# ardSCSInoV2.net
KiCad netlist of a schematic drawn in EAGLE
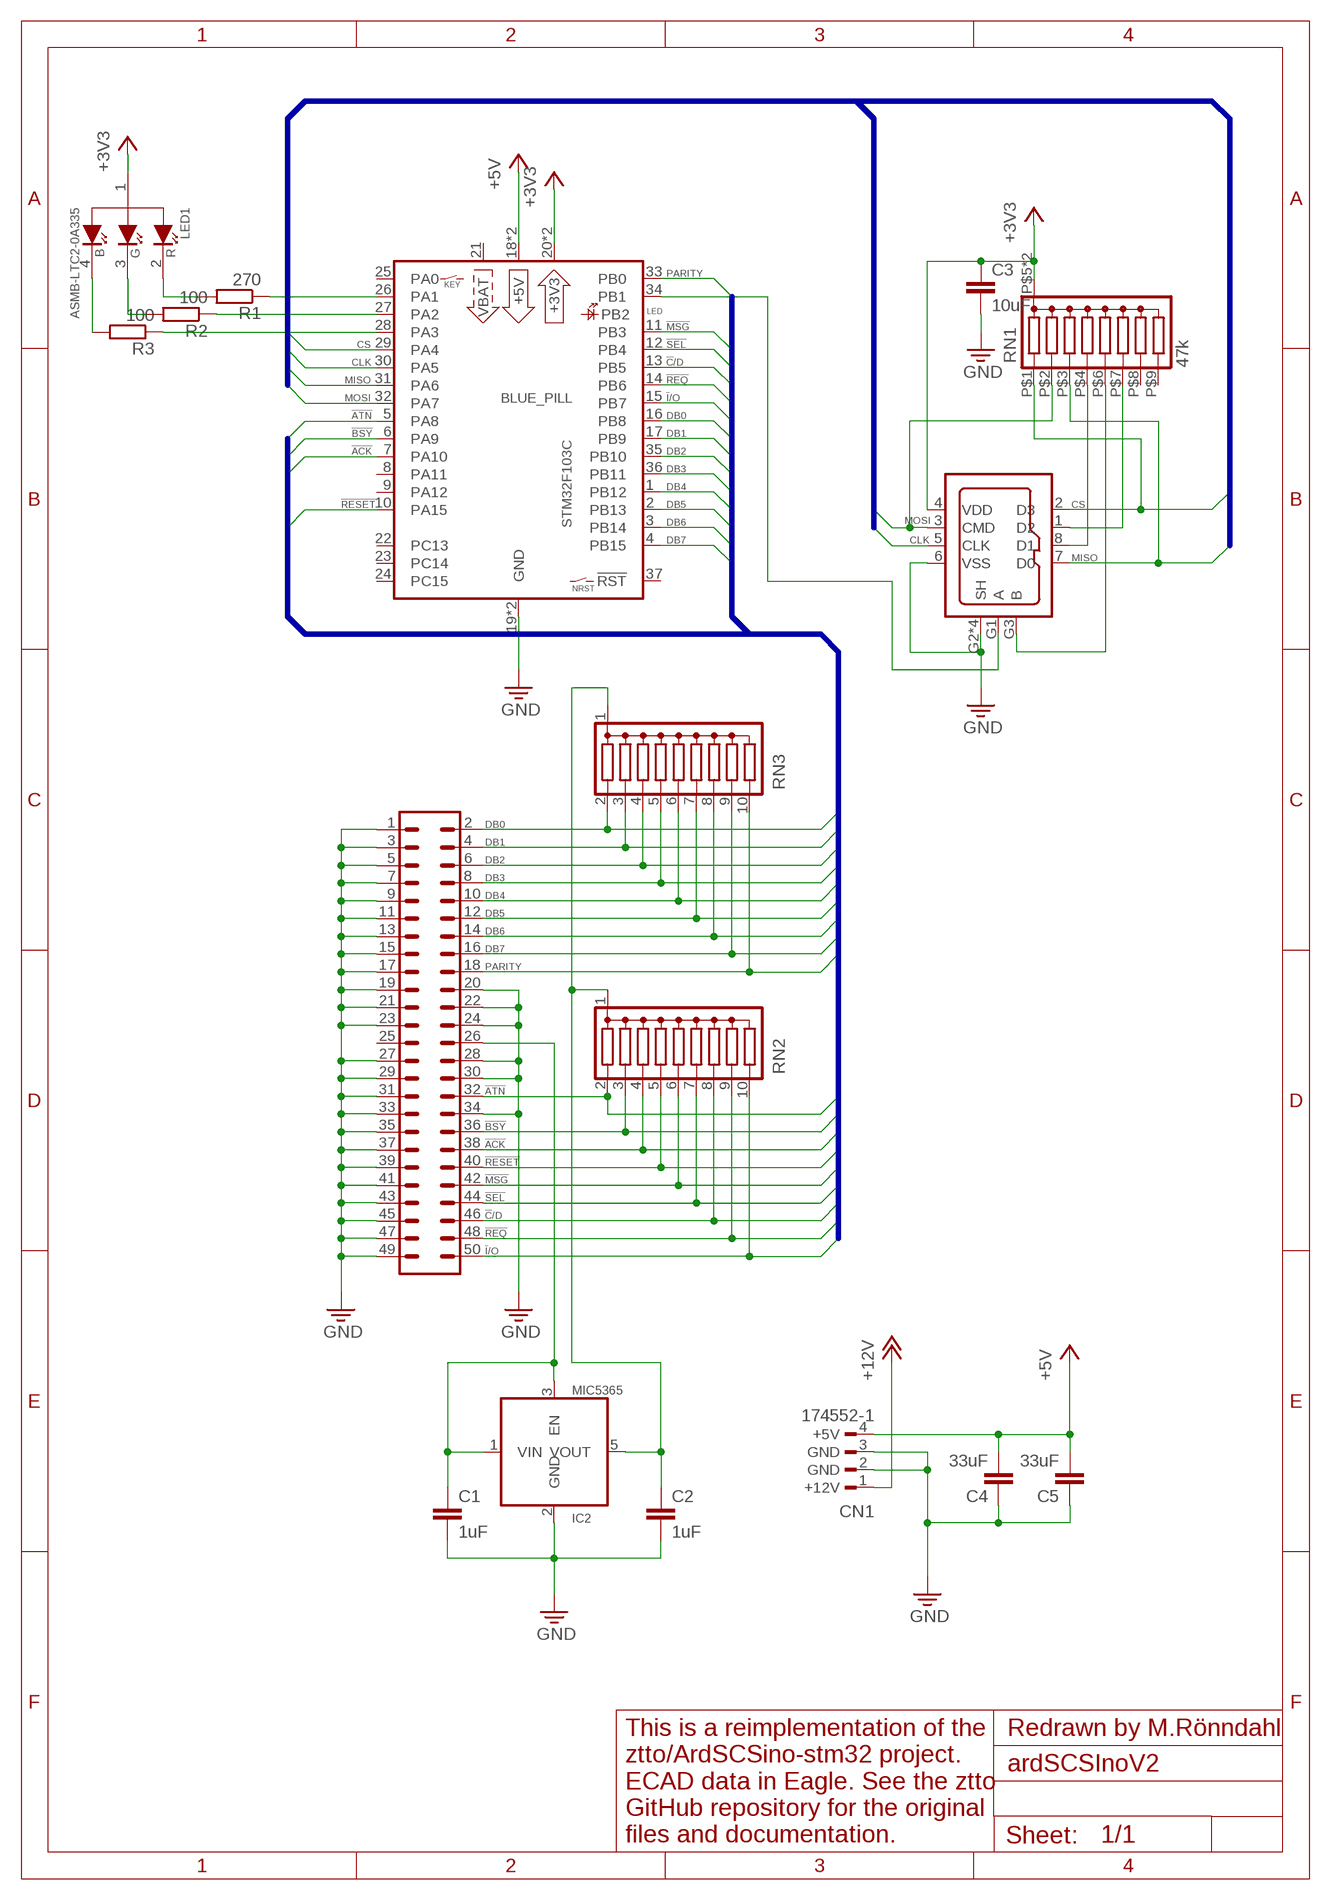
[diagram p0: schematic, sheet 1]

(export (version "E")
  (design (tool "Eeschema 10.0.6"))
  (components
    (comp (ref "BLUE_PILL")
      (value "STM32F103C")
      (footprint "eagle-import:B-PILL")
      (libsource (lib "eagle-import") (part "STM32F103C"))
    )
    (comp (ref "C1")
      (value "1uF")
      (footprint "eagle-import:C0805")
      (libsource (lib "eagle-import") (part "C-EUC0805"))
    )
    (comp (ref "C2")
      (value "1uF")
      (footprint "eagle-import:C0805")
      (libsource (lib "eagle-import") (part "C-EUC0805"))
    )
    (comp (ref "C3")
      (value "10uF")
      (footprint "eagle-import:C0805")
      (libsource (lib "eagle-import") (part "C-EUC0805"))
    )
    (comp (ref "C4")
      (value "33uF")
      (footprint "eagle-import:C0805")
      (libsource (lib "eagle-import") (part "C-EUC0805"))
    )
    (comp (ref "C5")
      (value "33uF")
      (footprint "eagle-import:C0805")
      (libsource (lib "eagle-import") (part "C-EUC0805"))
    )
    (comp (ref "CN1")
      (value "174552-1")
      (footprint "eagle-import:174552-1")
      (libsource (lib "eagle-import") (part "174552-1"))
    )
    (comp (ref "CN2")
      (value "30350-5002HB")
      (footprint "eagle-import:30350-5002")
      (libsource (lib "eagle-import") (part "30350-5002HB"))
    )
    (comp (ref "CN3")
      (value "DM3AT-SF-PEJM5-PD")
      (footprint "eagle-import:DM3AT-CL609")
      (libsource (lib "eagle-import") (part "DM3AT-SF-PEJM5-PD"))
    )
    (comp (ref "IC2")
      (value "MIC5365")
      (footprint "eagle-import:SOT23-5")
      (libsource (lib "eagle-import") (part "MIC5365"))
    )
    (comp (ref "LED1")
      (value "ASMB-LTC2-0A335")
      (footprint "eagle-import:PLCC-4_BROADCOM")
      (libsource (lib "eagle-import") (part "ASMB-LTC2-0A335"))
    )
    (comp (ref "R1")
      (value "270")
      (footprint "eagle-import:R0603")
      (libsource (lib "eagle-import") (part "R-EU_R0603"))
    )
    (comp (ref "R2")
      (value "100")
      (footprint "eagle-import:R0603")
      (libsource (lib "eagle-import") (part "R-EU_R0603"))
    )
    (comp (ref "R3")
      (value "100")
      (footprint "eagle-import:R0603")
      (libsource (lib "eagle-import") (part "R-EU_R0603"))
    )
    (comp (ref "RN1")
      (value "47k")
      (footprint "eagle-import:PANAS-2512")
      (libsource (lib "eagle-import") (part "EXB-A10P"))
    )
    (comp (ref "RN2")
      (value "RNY9")
      (footprint "eagle-import:RN-10")
      (libsource (lib "eagle-import") (part "RNY9"))
    )
    (comp (ref "RN3")
      (value "RNY9")
      (footprint "eagle-import:RN-10")
      (libsource (lib "eagle-import") (part "RNY9"))
    )
  )
  (nets
    (net (code "1") (name "+3V3") (class "Default")
      (node (ref "BLUE_PILL") (pin "20") (pinfunction "+3V3_20") (pintype "power_in"))
      (node (ref "BLUE_PILL") (pin "38") (pinfunction "+3V3_38") (pintype "power_in"))
      (node (ref "C3") (pin "1") (pinfunction "1_1") (pintype "passive"))
      (node (ref "CN3") (pin "4") (pinfunction "VDD_4") (pintype "power_in"))
      (node (ref "LED1") (pin "1") (pinfunction "CA_1") (pintype "bidirectional"))
      (node (ref "RN1") (pin "P$10") (pinfunction "C_P$10") (pintype "passive"))
      (node (ref "RN1") (pin "P$5") (pinfunction "C_P$5") (pintype "passive"))
    )
    (net (code "2") (name "+5V") (class "Default")
      (node (ref "BLUE_PILL") (pin "18") (pinfunction "+5V_18") (pintype "power_in"))
      (node (ref "BLUE_PILL") (pin "40") (pinfunction "+5V_40") (pintype "power_in"))
      (node (ref "C4") (pin "2") (pinfunction "2_2") (pintype "passive"))
      (node (ref "C5") (pin "2") (pinfunction "2_2") (pintype "passive"))
      (node (ref "CN1") (pin "4") (pinfunction "+5V_4") (pintype "passive"))
    )
    (net (code "3") (name "+12V") (class "Default")
      (node (ref "CN1") (pin "1") (pinfunction "+12V_1") (pintype "passive"))
    )
    (net (code "4") (name "/CLK") (class "Default")
      (node (ref "BLUE_PILL") (pin "30") (pinfunction "PA5_30") (pintype "bidirectional"))
      (node (ref "CN3") (pin "5") (pinfunction "CLK_5") (pintype "input"))
    )
    (net (code "5") (name "/CS") (class "Default")
      (node (ref "BLUE_PILL") (pin "29") (pinfunction "PA4_29") (pintype "bidirectional"))
      (node (ref "CN3") (pin "2") (pinfunction "D3_2") (pintype "bidirectional"))
      (node (ref "RN1") (pin "P$1") (pinfunction "1_P$1") (pintype "passive"))
    )
    (net (code "6") (name "/DB0") (class "Default")
      (node (ref "BLUE_PILL") (pin "16") (pinfunction "PB8_16") (pintype "bidirectional"))
      (node (ref "CN2") (pin "2") (pinfunction "2_2") (pintype "passive"))
      (node (ref "RN3") (pin "2") (pinfunction "1_2") (pintype "passive"))
    )
    (net (code "7") (name "/DB1") (class "Default")
      (node (ref "BLUE_PILL") (pin "17") (pinfunction "PB9_17") (pintype "bidirectional"))
      (node (ref "CN2") (pin "4") (pinfunction "4_4") (pintype "passive"))
      (node (ref "RN3") (pin "3") (pinfunction "2_3") (pintype "passive"))
    )
    (net (code "8") (name "/DB2") (class "Default")
      (node (ref "BLUE_PILL") (pin "35") (pinfunction "PB10_35") (pintype "bidirectional"))
      (node (ref "CN2") (pin "6") (pinfunction "6_6") (pintype "passive"))
      (node (ref "RN3") (pin "4") (pinfunction "3_4") (pintype "passive"))
    )
    (net (code "9") (name "/DB3") (class "Default")
      (node (ref "BLUE_PILL") (pin "36") (pinfunction "PB11_36") (pintype "bidirectional"))
      (node (ref "CN2") (pin "8") (pinfunction "8_8") (pintype "passive"))
      (node (ref "RN3") (pin "5") (pinfunction "4_5") (pintype "passive"))
    )
    (net (code "10") (name "/DB4") (class "Default")
      (node (ref "BLUE_PILL") (pin "1") (pinfunction "PB12_1") (pintype "bidirectional"))
      (node (ref "CN2") (pin "10") (pinfunction "10_10") (pintype "passive"))
      (node (ref "RN3") (pin "6") (pinfunction "5_6") (pintype "passive"))
    )
    (net (code "11") (name "/DB5") (class "Default")
      (node (ref "BLUE_PILL") (pin "2") (pinfunction "PB13_2") (pintype "bidirectional"))
      (node (ref "CN2") (pin "12") (pinfunction "12_12") (pintype "passive"))
      (node (ref "RN3") (pin "7") (pinfunction "6_7") (pintype "passive"))
    )
    (net (code "12") (name "/DB6") (class "Default")
      (node (ref "BLUE_PILL") (pin "3") (pinfunction "PB14_3") (pintype "bidirectional"))
      (node (ref "CN2") (pin "14") (pinfunction "14_14") (pintype "passive"))
      (node (ref "RN3") (pin "8") (pinfunction "7_8") (pintype "passive"))
    )
    (net (code "13") (name "/DB7") (class "Default")
      (node (ref "BLUE_PILL") (pin "4") (pinfunction "PB15_4") (pintype "bidirectional"))
      (node (ref "CN2") (pin "16") (pinfunction "16_16") (pintype "passive"))
      (node (ref "RN3") (pin "9") (pinfunction "8_9") (pintype "passive"))
    )
    (net (code "14") (name "/MISO") (class "Default")
      (node (ref "BLUE_PILL") (pin "31") (pinfunction "PA6_31") (pintype "bidirectional"))
      (node (ref "CN3") (pin "7") (pinfunction "D0_7") (pintype "bidirectional"))
      (node (ref "RN1") (pin "P$3") (pinfunction "3_P$3") (pintype "passive"))
    )
    (net (code "15") (name "/MOSI") (class "Default")
      (node (ref "BLUE_PILL") (pin "32") (pinfunction "PA7_32") (pintype "bidirectional"))
      (node (ref "CN3") (pin "3") (pinfunction "CMD_3") (pintype "input"))
      (node (ref "RN1") (pin "P$2") (pinfunction "2_P$2") (pintype "passive"))
    )
    (net (code "16") (name "/PARITY") (class "Default")
      (node (ref "BLUE_PILL") (pin "33") (pinfunction "PB0_33") (pintype "bidirectional"))
      (node (ref "CN2") (pin "18") (pinfunction "18_18") (pintype "passive"))
      (node (ref "RN3") (pin "10") (pinfunction "9_10") (pintype "passive"))
    )
    (net (code "17") (name "/VBAT") (class "Default")
      (node (ref "BLUE_PILL") (pin "21") (pinfunction "VBAT_21") (pintype "power_in"))
    )
    (net (code "18") (name "/~{ACK}") (class "Default")
      (node (ref "BLUE_PILL") (pin "7") (pinfunction "PA10_7") (pintype "bidirectional"))
      (node (ref "CN2") (pin "38") (pinfunction "38_38") (pintype "passive"))
      (node (ref "RN2") (pin "4") (pinfunction "3_4") (pintype "passive"))
    )
    (net (code "19") (name "/~{ATN}") (class "Default")
      (node (ref "BLUE_PILL") (pin "5") (pinfunction "PA8_5") (pintype "bidirectional"))
      (node (ref "CN2") (pin "32") (pinfunction "32_32") (pintype "passive"))
      (node (ref "RN2") (pin "2") (pinfunction "1_2") (pintype "passive"))
    )
    (net (code "20") (name "/~{BSY}") (class "Default")
      (node (ref "BLUE_PILL") (pin "6") (pinfunction "PA9_6") (pintype "bidirectional"))
      (node (ref "CN2") (pin "36") (pinfunction "36_36") (pintype "passive"))
      (node (ref "RN2") (pin "3") (pinfunction "2_3") (pintype "passive"))
    )
    (net (code "21") (name "/~{C}{slash}D") (class "Default")
      (node (ref "BLUE_PILL") (pin "13") (pinfunction "PB5_13") (pintype "bidirectional"))
      (node (ref "CN2") (pin "46") (pinfunction "46_46") (pintype "passive"))
      (node (ref "RN2") (pin "8") (pinfunction "7_8") (pintype "passive"))
    )
    (net (code "22") (name "/~{I}{slash}O") (class "Default")
      (node (ref "BLUE_PILL") (pin "15") (pinfunction "PB7_15") (pintype "bidirectional"))
      (node (ref "CN2") (pin "50") (pinfunction "50_50") (pintype "passive"))
      (node (ref "RN2") (pin "10") (pinfunction "9_10") (pintype "passive"))
    )
    (net (code "23") (name "/~{MSG}") (class "Default")
      (node (ref "BLUE_PILL") (pin "11") (pinfunction "PB3_11") (pintype "bidirectional"))
      (node (ref "CN2") (pin "42") (pinfunction "42_42") (pintype "passive"))
      (node (ref "RN2") (pin "6") (pinfunction "5_6") (pintype "passive"))
    )
    (net (code "24") (name "/~{REQ}") (class "Default")
      (node (ref "BLUE_PILL") (pin "14") (pinfunction "PB6_14") (pintype "bidirectional"))
      (node (ref "CN2") (pin "48") (pinfunction "48_48") (pintype "passive"))
      (node (ref "RN2") (pin "9") (pinfunction "8_9") (pintype "passive"))
    )
    (net (code "25") (name "/~{RESET}") (class "Default")
      (node (ref "BLUE_PILL") (pin "10") (pinfunction "PA15_10") (pintype "bidirectional"))
      (node (ref "CN2") (pin "40") (pinfunction "40_40") (pintype "passive"))
      (node (ref "RN2") (pin "5") (pinfunction "4_5") (pintype "passive"))
    )
    (net (code "26") (name "/~{SEL}") (class "Default")
      (node (ref "BLUE_PILL") (pin "12") (pinfunction "PB4_12") (pintype "bidirectional"))
      (node (ref "CN2") (pin "44") (pinfunction "44_44") (pintype "passive"))
      (node (ref "RN2") (pin "7") (pinfunction "6_7") (pintype "passive"))
    )
    (net (code "27") (name "GND") (class "Default")
      (node (ref "BLUE_PILL") (pin "19") (pinfunction "GND_19") (pintype "power_in"))
      (node (ref "BLUE_PILL") (pin "39") (pinfunction "GND_39") (pintype "power_in"))
      (node (ref "C1") (pin "2") (pinfunction "2_2") (pintype "passive"))
      (node (ref "C2") (pin "2") (pinfunction "2_2") (pintype "passive"))
      (node (ref "C3") (pin "2") (pinfunction "2_2") (pintype "passive"))
      (node (ref "C4") (pin "1") (pinfunction "1_1") (pintype "passive"))
      (node (ref "C5") (pin "1") (pinfunction "1_1") (pintype "passive"))
      (node (ref "CN1") (pin "2") (pinfunction "GND_2") (pintype "passive"))
      (node (ref "CN1") (pin "3") (pinfunction "GND_3") (pintype "passive"))
      (node (ref "CN2") (pin "1") (pinfunction "1_1") (pintype "passive"))
      (node (ref "CN2") (pin "11") (pinfunction "11_11") (pintype "passive"))
      (node (ref "CN2") (pin "13") (pinfunction "13_13") (pintype "passive"))
      (node (ref "CN2") (pin "15") (pinfunction "15_15") (pintype "passive"))
      (node (ref "CN2") (pin "17") (pinfunction "17_17") (pintype "passive"))
      (node (ref "CN2") (pin "19") (pinfunction "19_19") (pintype "passive"))
      (node (ref "CN2") (pin "20") (pinfunction "20_20") (pintype "passive"))
      (node (ref "CN2") (pin "21") (pinfunction "21_21") (pintype "passive"))
      (node (ref "CN2") (pin "22") (pinfunction "22_22") (pintype "passive"))
      (node (ref "CN2") (pin "23") (pinfunction "23_23") (pintype "passive"))
      (node (ref "CN2") (pin "24") (pinfunction "24_24") (pintype "passive"))
      (node (ref "CN2") (pin "27") (pinfunction "27_27") (pintype "passive"))
      (node (ref "CN2") (pin "28") (pinfunction "28_28") (pintype "passive"))
      (node (ref "CN2") (pin "29") (pinfunction "29_29") (pintype "passive"))
      (node (ref "CN2") (pin "3") (pinfunction "3_3") (pintype "passive"))
      (node (ref "CN2") (pin "30") (pinfunction "30_30") (pintype "passive"))
      (node (ref "CN2") (pin "31") (pinfunction "31_31") (pintype "passive"))
      (node (ref "CN2") (pin "33") (pinfunction "33_33") (pintype "passive"))
      (node (ref "CN2") (pin "34") (pinfunction "34_34") (pintype "passive"))
      (node (ref "CN2") (pin "35") (pinfunction "35_35") (pintype "passive"))
      (node (ref "CN2") (pin "37") (pinfunction "37_37") (pintype "passive"))
      (node (ref "CN2") (pin "39") (pinfunction "39_39") (pintype "passive"))
      (node (ref "CN2") (pin "41") (pinfunction "41_41") (pintype "passive"))
      (node (ref "CN2") (pin "43") (pinfunction "43_43") (pintype "passive"))
      (node (ref "CN2") (pin "45") (pinfunction "45_45") (pintype "passive"))
      (node (ref "CN2") (pin "47") (pinfunction "47_47") (pintype "passive"))
      (node (ref "CN2") (pin "49") (pinfunction "49_49") (pintype "passive"))
      (node (ref "CN2") (pin "5") (pinfunction "5_5") (pintype "passive"))
      (node (ref "CN2") (pin "7") (pinfunction "7_7") (pintype "passive"))
      (node (ref "CN2") (pin "9") (pinfunction "9_9") (pintype "passive"))
      (node (ref "CN3") (pin "6") (pinfunction "VSS_6") (pintype "power_in"))
      (node (ref "CN3") (pin "G2") (pinfunction "SH_G2") (pintype "passive"))
      (node (ref "CN3") (pin "G4") (pinfunction "SH_G4") (pintype "passive"))
      (node (ref "CN3") (pin "G5") (pinfunction "SH_G5") (pintype "passive"))
      (node (ref "CN3") (pin "G6") (pinfunction "SH_G6") (pintype "passive"))
      (node (ref "IC2") (pin "2") (pinfunction "GND_2") (pintype "power_in"))
    )
    (net (code "28") (name "Net-(BLUE_PILL-PA1)") (class "Default")
      (node (ref "BLUE_PILL") (pin "26") (pinfunction "PA1_26") (pintype "bidirectional"))
      (node (ref "R1") (pin "1") (pinfunction "1_1") (pintype "passive"))
    )
    (net (code "29") (name "Net-(BLUE_PILL-PA2)") (class "Default")
      (node (ref "BLUE_PILL") (pin "27") (pinfunction "PA2_27") (pintype "bidirectional"))
      (node (ref "R2") (pin "1") (pinfunction "1_1") (pintype "passive"))
    )
    (net (code "30") (name "Net-(BLUE_PILL-PA3)") (class "Default")
      (node (ref "BLUE_PILL") (pin "28") (pinfunction "PA3_28") (pintype "bidirectional"))
      (node (ref "R3") (pin "1") (pinfunction "1_1") (pintype "passive"))
    )
    (net (code "31") (name "Net-(BLUE_PILL-PB1)") (class "Default")
      (node (ref "BLUE_PILL") (pin "34") (pinfunction "PB1_34") (pintype "bidirectional"))
      (node (ref "CN3") (pin "G1") (pinfunction "A_G1") (pintype "passive"))
    )
    (net (code "32") (name "Net-(CN3-B)") (class "Default")
      (node (ref "CN3") (pin "G3") (pinfunction "B_G3") (pintype "passive"))
      (node (ref "RN1") (pin "P$6") (pinfunction "5_P$6") (pintype "passive"))
    )
    (net (code "33") (name "Net-(CN3-D1)") (class "Default")
      (node (ref "CN3") (pin "8") (pinfunction "D1_8") (pintype "bidirectional"))
      (node (ref "RN1") (pin "P$4") (pinfunction "4_P$4") (pintype "passive"))
    )
    (net (code "34") (name "Net-(CN3-D2)") (class "Default")
      (node (ref "CN3") (pin "1") (pinfunction "D2_1") (pintype "bidirectional"))
      (node (ref "RN1") (pin "P$7") (pinfunction "6_P$7") (pintype "passive"))
    )
    (net (code "35") (name "Net-(IC2-EN)") (class "Default")
      (node (ref "C1") (pin "1") (pinfunction "1_1") (pintype "passive"))
      (node (ref "CN2") (pin "26") (pinfunction "26_26") (pintype "passive"))
      (node (ref "IC2") (pin "1") (pinfunction "VIN_1") (pintype "power_in"))
      (node (ref "IC2") (pin "3") (pinfunction "EN_3") (pintype "input"))
    )
    (net (code "36") (name "Net-(IC2-VOUT)") (class "Default")
      (node (ref "C2") (pin "1") (pinfunction "1_1") (pintype "passive"))
      (node (ref "IC2") (pin "5") (pinfunction "VOUT_5") (pintype "power_in"))
      (node (ref "RN2") (pin "1") (pinfunction "C_1") (pintype "passive"))
      (node (ref "RN3") (pin "1") (pinfunction "C_1") (pintype "passive"))
    )
    (net (code "37") (name "Net-(LED1-B)") (class "Default")
      (node (ref "LED1") (pin "4") (pinfunction "B_4") (pintype "bidirectional"))
      (node (ref "R3") (pin "2") (pinfunction "2_2") (pintype "passive"))
    )
    (net (code "38") (name "Net-(LED1-G)") (class "Default")
      (node (ref "LED1") (pin "3") (pinfunction "G_3") (pintype "bidirectional"))
      (node (ref "R2") (pin "2") (pinfunction "2_2") (pintype "passive"))
    )
    (net (code "39") (name "Net-(LED1-R)") (class "Default")
      (node (ref "LED1") (pin "2") (pinfunction "R_2") (pintype "bidirectional"))
      (node (ref "R1") (pin "2") (pinfunction "2_2") (pintype "passive"))
    )
    (net (code "40") (name "unconnected-(BLUE_PILL-PA0-Pad25)") (class "Default")
      (node (ref "BLUE_PILL") (pin "25") (pinfunction "PA0_25") (pintype "bidirectional"))
    )
    (net (code "41") (name "unconnected-(BLUE_PILL-PA11-Pad8)") (class "Default")
      (node (ref "BLUE_PILL") (pin "8") (pinfunction "PA11_8") (pintype "bidirectional"))
    )
    (net (code "42") (name "unconnected-(BLUE_PILL-PA12-Pad9)") (class "Default")
      (node (ref "BLUE_PILL") (pin "9") (pinfunction "PA12_9") (pintype "bidirectional"))
    )
    (net (code "43") (name "unconnected-(BLUE_PILL-PC13-Pad22)") (class "Default")
      (node (ref "BLUE_PILL") (pin "22") (pinfunction "PC13_22") (pintype "bidirectional"))
    )
    (net (code "44") (name "unconnected-(BLUE_PILL-PC14-Pad23)") (class "Default")
      (node (ref "BLUE_PILL") (pin "23") (pinfunction "PC14_23") (pintype "bidirectional"))
    )
    (net (code "45") (name "unconnected-(BLUE_PILL-PC15-Pad24)") (class "Default")
      (node (ref "BLUE_PILL") (pin "24") (pinfunction "PC15_24") (pintype "bidirectional"))
    )
    (net (code "46") (name "unconnected-(BLUE_PILL-~{RST}-Pad37)") (class "Default")
      (node (ref "BLUE_PILL") (pin "37") (pinfunction "~{RST}_37") (pintype "input"))
    )
    (net (code "47") (name "unconnected-(CN2-Pad25)") (class "Default")
      (node (ref "CN2") (pin "25") (pinfunction "25_25") (pintype "passive"))
    )
    (net (code "48") (name "unconnected-(RN1-7-PadP$8)") (class "Default")
      (node (ref "RN1") (pin "P$8") (pinfunction "7_P$8") (pintype "passive"))
    )
    (net (code "49") (name "unconnected-(RN1-8-PadP$9)") (class "Default")
      (node (ref "RN1") (pin "P$9") (pinfunction "8_P$9") (pintype "passive"))
    )
  )
)
